# Power.net
KiCad netlist of a schematic drawn in Altium Designer
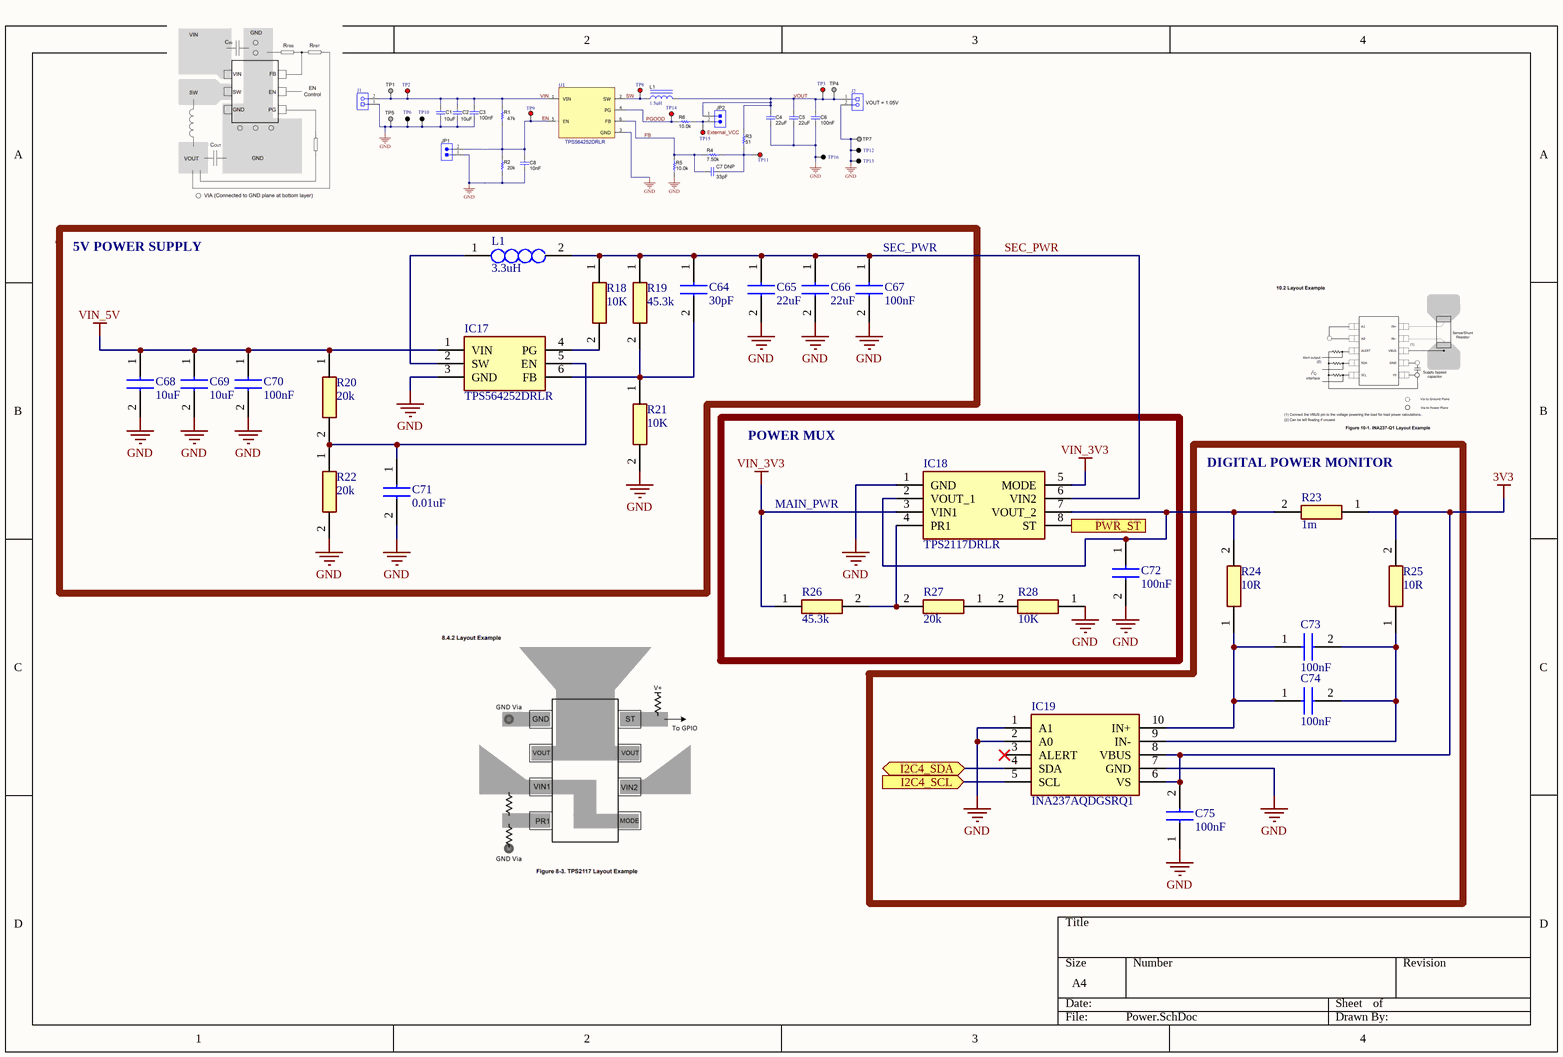
[diagram p0: Power.SchDoc]

(export (version "E")
  (design (tool "Eeschema 10.0.6"))
  (components
    (comp (ref "C64")
      (value "30pF")
      (footprint "RT_IS:C0603")
      (description "30 pF ±1% 50V Ceramic Capacitor X8R 0603 (1608 Metric)")
      (fields
        (field (name "MANUFACTURER_PART_NUMBER") "C0603C300F5HACAUTO")
        (field (name "MOUSER PART NUMBER") "80-C0603C300F5HAUTO")
      )
      (libsource (lib "*") (part "C0603C300F5HACAUTO"))
    )
    (comp (ref "C65")
      (value "22uF")
      (footprint "RT_IS:CAPC1608X90N")
      (description "22 µF ±20% 10V Ceramic Capacitor X5R 0603 (1608 Metric)")
      (fields
        (field (name "MANUFACTURER_PART_NUMBER") "GRT188R61A226ME13D")
        (field (name "MOUSER PART NUMBER") "81-GRT188R61A226ME13")
      )
      (libsource (lib "*") (part "GRT188R61A226ME13D"))
    )
    (comp (ref "C66")
      (value "22uF")
      (footprint "RT_IS:CAPC1608X90N")
      (description "22 µF ±20% 10V Ceramic Capacitor X5R 0603 (1608 Metric)")
      (fields
        (field (name "MANUFACTURER_PART_NUMBER") "GRT188R61A226ME13D")
        (field (name "MOUSER PART NUMBER") "81-GRT188R61A226ME13")
      )
      (libsource (lib "*") (part "GRT188R61A226ME13D"))
    )
    (comp (ref "C67")
      (value "100nF")
      (footprint "RT_IS:CAPC1608X95N")
      (description "0.1 µF ±20% 16V Ceramic Capacitor X7R 0603 (1608 Metric)")
      (fields (field (name "MANUFACTURER_PART_NUMBER") "C0603C104M4RAC7867"))
      (libsource (lib "*") (part "C0603C104M4RAC7867"))
    )
    (comp (ref "C68")
      (value "10uF")
      (footprint "RT_IS:CAPC1608X90N")
      (description "CAP CER 10UF 10V X7T 0603")
      (fields
        (field (name "MANUFACTURER_PART_NUMBER") "GRM188D71A106KA73D")
        (field (name "MOUSER PART NUMBER") "81-GRM188D71A106KA3D")
      )
      (libsource (lib "*") (part "GRM188D71A106KA73D"))
    )
    (comp (ref "C69")
      (value "10uF")
      (footprint "RT_IS:CAPC1608X90N")
      (description "CAP CER 10UF 10V X7T 0603")
      (fields
        (field (name "MANUFACTURER_PART_NUMBER") "GRM188D71A106KA73D")
        (field (name "MOUSER PART NUMBER") "81-GRM188D71A106KA3D")
      )
      (libsource (lib "*") (part "GRM188D71A106KA73D"))
    )
    (comp (ref "C70")
      (value "100nF")
      (footprint "RT_IS:CAPC1608X95N")
      (description "0.1 µF ±20% 16V Ceramic Capacitor X7R 0603 (1608 Metric)")
      (fields (field (name "MANUFACTURER_PART_NUMBER") "C0603C104M4RAC7867"))
      (libsource (lib "*") (part "C0603C104M4RAC7867"))
    )
    (comp (ref "C71")
      (value "0.01uF")
      (footprint "RT_IS:C0603")
      (description "10000 pF ±10% 63V Ceramic Capacitor X7R 0603 (1608 Metric)")
      (fields
        (field (name "MANUFACTURER_PART_NUMBER") "C0603C103KMRECAUTO")
        (field (name "MOUSER PART NUMBER") "80-C0603C103KMREAUTO")
      )
      (libsource (lib "*") (part "C0603C103KMRECAUTO"))
    )
    (comp (ref "C72")
      (value "100nF")
      (footprint "RT_IS:CAPC1608X95N")
      (description "0.1 µF ±20% 16V Ceramic Capacitor X7R 0603 (1608 Metric)")
      (fields (field (name "MANUFACTURER_PART_NUMBER") "C0603C104M4RAC7867"))
      (libsource (lib "*") (part "C0603C104M4RAC7867"))
    )
    (comp (ref "C73")
      (value "100nF")
      (footprint "RT_IS:CAPC1608X95N")
      (description "0.1 µF ±20% 16V Ceramic Capacitor X7R 0603 (1608 Metric)")
      (fields (field (name "MANUFACTURER_PART_NUMBER") "C0603C104M4RAC7867"))
      (libsource (lib "*") (part "C0603C104M4RAC7867"))
    )
    (comp (ref "C74")
      (value "100nF")
      (footprint "RT_IS:CAPC1608X95N")
      (description "0.1 µF ±20% 16V Ceramic Capacitor X7R 0603 (1608 Metric)")
      (fields (field (name "MANUFACTURER_PART_NUMBER") "C0603C104M4RAC7867"))
      (libsource (lib "*") (part "C0603C104M4RAC7867"))
    )
    (comp (ref "C75")
      (value "100nF")
      (footprint "RT_IS:CAPC1608X95N")
      (description "0.1 µF ±20% 16V Ceramic Capacitor X7R 0603 (1608 Metric)")
      (fields (field (name "MANUFACTURER_PART_NUMBER") "C0603C104M4RAC7867"))
      (libsource (lib "*") (part "C0603C104M4RAC7867"))
    )
    (comp (ref "IC17")
      (value "TPS564252DRLR")
      (footprint "RT_IS:SOTFL50P160X60-6N")
      (description "TPS564252DRLR\r\nBuck Switching Regulator IC Positive Adjustable 0.6V 1 Output 4A SOT-563, SOT-666")
      (fields
        (field (name "MANUFACTURER_PART_NUMBER") "TPS564257DRLR")
        (field (name "MOUSER PART NUMBER") "595-TPS564257DRLR")
      )
      (libsource (lib "*") (part "TPS564257DRLR"))
    )
    (comp (ref "IC18")
      (value "TPS2117DRLR")
      (footprint "RT_IS:SOTFL50P160X60-8N")
      (description "Power Switch/Driver 1:1 N-Channel 4A SOT-583")
      (fields
        (field (name "MANUFACTURER_PART_NUMBER") "TPS2116DRLR")
        (field (name "MOUSER PART NUMBER") "595-TPS2116DRLR")
      )
      (libsource (lib "*") (part "TPS2116DRLR"))
    )
    (comp (ref "IC19")
      (value "INA237AQDGSRQ1")
      (footprint "RT_IS:SOP50P490X110-10N")
      (description "Power Supply Controller 10-VSSOP")
      (fields (field (name "MOUSER PART NUMBER") "595-INA237AQDGSRQ1"))
      (libsource (lib "*") (part "INA237AQDGSRQ1"))
    )
    (comp (ref "L1")
      (value "3.3uH")
      (footprint "RT_IS:INDPM5653X430N")
      (description "3.3 µH Shielded Wirewound Inductor 5.75 A 18.5mOhm 2-SMD")
      (fields
        (field (name "MANUFACTURER_PART_NUMBER") "744316330")
        (field (name "MOUSER PART NUMBER") "710-744316330")
      )
      (libsource (lib "*") (part "744316330"))
    )
    (comp (ref "R18")
      (value "10K")
      (footprint "RT_IS:RESC1508X50N")
      (description "10 kOhms ±1% 0.125W, 1/8W Chip Resistor 0603 (1608 Metric) Anti-Sulfur Thin Film")
      (fields
        (field (name "MANUFACTURER_PART_NUMBER") "RNCP0603FTD10K0")
        (field (name "MOUSER PART NUMBER") "708-RNCP0603FTD10K0")
      )
      (libsource (lib "*") (part "RNCP0603FTD10K0"))
    )
    (comp (ref "R19")
      (value "45.3k")
      (footprint "RT_IS:RESC1608X55N")
      (description "45.3 kOhms ±1% 0.1W, 1/10W Chip Resistor 0603 (1608 Metric) Automotive AEC-Q200 Thick Film")
      (fields (field (name "MANUFACTURER_PART_NUMBER") "RMCF0603FT45K3"))
      (libsource (lib "*") (part "RMCF0603FT45K3"))
    )
    (comp (ref "R20")
      (value "20k")
      (footprint "RT_IS:RESC1608X55N")
      (description "20 kOhms ±1% 0.1W, 1/10W Chip Resistor 0603 (1608 Metric) Automotive AEC-Q200 Thick Film")
      (fields
        (field (name "MANUFACTURER_PART_NUMBER") "ERJ-3EKF2002V")
        (field (name "MOUSER PART NUMBER") "667-ERJ-3EKF2002V")
      )
      (libsource (lib "*") (part "ERJ-3EKF2002V"))
    )
    (comp (ref "R21")
      (value "10K")
      (footprint "RT_IS:RESC1508X50N")
      (description "10 kOhms ±1% 0.125W, 1/8W Chip Resistor 0603 (1608 Metric) Anti-Sulfur Thin Film")
      (fields
        (field (name "MANUFACTURER_PART_NUMBER") "RNCP0603FTD10K0")
        (field (name "MOUSER PART NUMBER") "708-RNCP0603FTD10K0")
      )
      (libsource (lib "*") (part "RNCP0603FTD10K0"))
    )
    (comp (ref "R22")
      (value "20k")
      (footprint "RT_IS:RESC1608X55N")
      (description "20 kOhms ±1% 0.1W, 1/10W Chip Resistor 0603 (1608 Metric) Automotive AEC-Q200 Thick Film")
      (fields
        (field (name "MANUFACTURER_PART_NUMBER") "ERJ-3EKF2002V")
        (field (name "MOUSER PART NUMBER") "667-ERJ-3EKF2002V")
      )
      (libsource (lib "*") (part "ERJ-3EKF2002V"))
    )
    (comp (ref "R23")
      (value "1m")
      (footprint "RT_IS:RESC2012X80N")
      (fields
        (field (name "MANUFACTURER_PART_NUMBER") "CRF0805-FZ-R001ELF")
        (field (name "MOUSER PART NUMBER") "652-CRF0805FZR001ELF")
      )
      (libsource (lib "*") (part "CRF0805-FZ-R001ELF"))
    )
    (comp (ref "R24")
      (value "10R")
      (footprint "RT_IS:RESC1608X55N")
      (description "10 Ohms ±1% 0.1W, 1/10W Chip Resistor 0603 (1608 Metric) Automotive AEC-Q200 Thick Film")
      (fields
        (field (name "MANUFACTURER_PART_NUMBER") "ERJ-3EKF10R0V")
        (field (name "MOUSER PART NUMBER") "667-ERJ-3EKF10R0V")
      )
      (libsource (lib "*") (part "ERJ-3EKF10R0V"))
    )
    (comp (ref "R25")
      (value "10R")
      (footprint "RT_IS:RESC1608X55N")
      (description "10 Ohms ±1% 0.1W, 1/10W Chip Resistor 0603 (1608 Metric) Automotive AEC-Q200 Thick Film")
      (fields
        (field (name "MANUFACTURER_PART_NUMBER") "ERJ-3EKF10R0V")
        (field (name "MOUSER PART NUMBER") "667-ERJ-3EKF10R0V")
      )
      (libsource (lib "*") (part "ERJ-3EKF10R0V"))
    )
    (comp (ref "R26")
      (value "45.3k")
      (footprint "RT_IS:RESC1608X55N")
      (description "45.3 kOhms ±1% 0.1W, 1/10W Chip Resistor 0603 (1608 Metric) Automotive AEC-Q200 Thick Film")
      (fields (field (name "MANUFACTURER_PART_NUMBER") "RMCF0603FT45K3"))
      (libsource (lib "") (part "RMCF0603FT45K3_1"))
    )
    (comp (ref "R27")
      (value "20k")
      (footprint "RT_IS:RESC1608X55N")
      (description "20 kOhms ±1% 0.1W, 1/10W Chip Resistor 0603 (1608 Metric) Automotive AEC-Q200 Thick Film")
      (fields
        (field (name "MANUFACTURER_PART_NUMBER") "ERJ-3EKF2002V")
        (field (name "MOUSER PART NUMBER") "667-ERJ-3EKF2002V")
      )
      (libsource (lib "") (part "ERJ-3EKF2002V_1"))
    )
    (comp (ref "R28")
      (value "10K")
      (footprint "RT_IS:RESC1508X50N")
      (description "10 kOhms ±1% 0.125W, 1/8W Chip Resistor 0603 (1608 Metric) Anti-Sulfur Thin Film")
      (fields
        (field (name "MANUFACTURER_PART_NUMBER") "RNCP0603FTD10K0")
        (field (name "MOUSER PART NUMBER") "708-RNCP0603FTD10K0")
      )
      (libsource (lib "") (part "RNCP0603FTD10K0_1"))
    )
  )
  (nets
    (net (code "1") (name "/I2C4_SCL") (class "Default")
      (node (ref "IC19") (pin "5") (pinfunction "SCL_5") (pintype "passive"))
    )
    (net (code "2") (name "/I2C4_SDA") (class "Default")
      (node (ref "IC19") (pin "4") (pinfunction "SDA_4") (pintype "passive"))
    )
    (net (code "3") (name "/PWR_ST") (class "Default")
      (node (ref "IC18") (pin "8") (pinfunction "ST_8") (pintype "passive"))
    )
    (net (code "4") (name "/SEC_PWR") (class "Default")
      (node (ref "C64") (pin "1") (pinfunction "1_1") (pintype "passive"))
      (node (ref "C65") (pin "1") (pinfunction "1_1") (pintype "passive"))
      (node (ref "C66") (pin "1") (pinfunction "1_1") (pintype "passive"))
      (node (ref "C67") (pin "1") (pinfunction "1_1") (pintype "passive"))
      (node (ref "IC18") (pin "6") (pinfunction "VIN2_6") (pintype "passive"))
      (node (ref "L1") (pin "2") (pinfunction "2_2") (pintype "passive"))
      (node (ref "R18") (pin "1") (pinfunction "1_1") (pintype "passive"))
      (node (ref "R19") (pin "1") (pinfunction "1_1") (pintype "passive"))
    )
    (net (code "5") (name "3V3") (class "Default")
      (node (ref "C75") (pin "2") (pinfunction "2_2") (pintype "passive"))
      (node (ref "IC19") (pin "6") (pinfunction "VS_6") (pintype "passive"))
      (node (ref "IC19") (pin "8") (pinfunction "VBUS_8") (pintype "passive"))
      (node (ref "R23") (pin "1") (pinfunction "1_1") (pintype "passive"))
      (node (ref "R25") (pin "2") (pinfunction "2_2") (pintype "passive"))
    )
    (net (code "6") (name "GND") (class "Default")
      (node (ref "C65") (pin "2") (pinfunction "2_2") (pintype "passive"))
      (node (ref "C66") (pin "2") (pinfunction "2_2") (pintype "passive"))
      (node (ref "C67") (pin "2") (pinfunction "2_2") (pintype "passive"))
      (node (ref "C68") (pin "2") (pinfunction "2_2") (pintype "passive"))
      (node (ref "C69") (pin "2") (pinfunction "2_2") (pintype "passive"))
      (node (ref "C70") (pin "2") (pinfunction "2_2") (pintype "passive"))
      (node (ref "C71") (pin "2") (pinfunction "2_2") (pintype "passive"))
      (node (ref "C72") (pin "2") (pinfunction "2_2") (pintype "passive"))
      (node (ref "C75") (pin "1") (pinfunction "1_1") (pintype "passive"))
      (node (ref "IC17") (pin "3") (pinfunction "GND_3") (pintype "passive"))
      (node (ref "IC18") (pin "1") (pinfunction "GND_1") (pintype "passive"))
      (node (ref "IC19") (pin "1") (pinfunction "A1_1") (pintype "passive"))
      (node (ref "IC19") (pin "2") (pinfunction "A0_2") (pintype "passive"))
      (node (ref "IC19") (pin "7") (pinfunction "GND_7") (pintype "passive"))
      (node (ref "R21") (pin "2") (pinfunction "2_2") (pintype "passive"))
      (node (ref "R22") (pin "2") (pinfunction "2_2") (pintype "passive"))
      (node (ref "R28") (pin "1") (pinfunction "1_1") (pintype "passive"))
    )
    (net (code "7") (name "Net-(IC17-EN)") (class "Default")
      (node (ref "C71") (pin "1") (pinfunction "1_1") (pintype "passive"))
      (node (ref "IC17") (pin "5") (pinfunction "EN_5") (pintype "passive"))
      (node (ref "R20") (pin "2") (pinfunction "2_2") (pintype "passive"))
      (node (ref "R22") (pin "1") (pinfunction "1_1") (pintype "passive"))
    )
    (net (code "8") (name "Net-(IC17-FB)") (class "Default")
      (node (ref "C64") (pin "2") (pinfunction "2_2") (pintype "passive"))
      (node (ref "IC17") (pin "6") (pinfunction "FB_6") (pintype "passive"))
      (node (ref "R19") (pin "2") (pinfunction "2_2") (pintype "passive"))
      (node (ref "R21") (pin "1") (pinfunction "1_1") (pintype "passive"))
    )
    (net (code "9") (name "Net-(IC17-PG)") (class "Default")
      (node (ref "IC17") (pin "4") (pinfunction "PG_4") (pintype "passive"))
      (node (ref "R18") (pin "2") (pinfunction "2_2") (pintype "passive"))
    )
    (net (code "10") (name "Net-(IC17-SW)") (class "Default")
      (node (ref "IC17") (pin "2") (pinfunction "SW_2") (pintype "passive"))
      (node (ref "L1") (pin "1") (pinfunction "1_1") (pintype "passive"))
    )
    (net (code "11") (name "Net-(IC18-PR1)") (class "Default")
      (node (ref "IC18") (pin "4") (pinfunction "PR1_4") (pintype "passive"))
      (node (ref "R26") (pin "2") (pinfunction "2_2") (pintype "passive"))
      (node (ref "R27") (pin "2") (pinfunction "2_2") (pintype "passive"))
    )
    (net (code "12") (name "Net-(IC18-VOUT_1)") (class "Default")
      (node (ref "C72") (pin "1") (pinfunction "1_1") (pintype "passive"))
      (node (ref "IC18") (pin "2") (pinfunction "VOUT_1_2") (pintype "passive"))
      (node (ref "IC18") (pin "7") (pinfunction "VOUT_2_7") (pintype "passive"))
      (node (ref "R23") (pin "2") (pinfunction "2_2") (pintype "passive"))
      (node (ref "R24") (pin "2") (pinfunction "2_2") (pintype "passive"))
    )
    (net (code "13") (name "Net-(IC19-IN+)") (class "Default")
      (node (ref "C73") (pin "1") (pinfunction "1_1") (pintype "passive"))
      (node (ref "C74") (pin "1") (pinfunction "1_1") (pintype "passive"))
      (node (ref "IC19") (pin "10") (pinfunction "IN+_10") (pintype "passive"))
      (node (ref "R24") (pin "1") (pinfunction "1_1") (pintype "passive"))
    )
    (net (code "14") (name "Net-(IC19-IN-)") (class "Default")
      (node (ref "C73") (pin "2") (pinfunction "2_2") (pintype "passive"))
      (node (ref "C74") (pin "2") (pinfunction "2_2") (pintype "passive"))
      (node (ref "IC19") (pin "9") (pinfunction "IN-_9") (pintype "passive"))
      (node (ref "R25") (pin "1") (pinfunction "1_1") (pintype "passive"))
    )
    (net (code "15") (name "Net-(R27-Pad1)") (class "Default")
      (node (ref "R27") (pin "1") (pinfunction "1_1") (pintype "passive"))
      (node (ref "R28") (pin "2") (pinfunction "2_2") (pintype "passive"))
    )
    (net (code "16") (name "VIN_3V3") (class "Default")
      (node (ref "IC18") (pin "3") (pinfunction "VIN1_3") (pintype "passive"))
      (node (ref "IC18") (pin "5") (pinfunction "MODE_5") (pintype "passive"))
      (node (ref "R26") (pin "1") (pinfunction "1_1") (pintype "passive"))
    )
    (net (code "17") (name "VIN_5V") (class "Default")
      (node (ref "C68") (pin "1") (pinfunction "1_1") (pintype "passive"))
      (node (ref "C69") (pin "1") (pinfunction "1_1") (pintype "passive"))
      (node (ref "C70") (pin "1") (pinfunction "1_1") (pintype "passive"))
      (node (ref "IC17") (pin "1") (pinfunction "VIN_1") (pintype "passive"))
      (node (ref "R20") (pin "1") (pinfunction "1_1") (pintype "passive"))
    )
    (net (code "18") (name "unconnected-(IC19-ALERT-Pad3)") (class "Default")
      (node (ref "IC19") (pin "3") (pinfunction "ALERT_3") (pintype "passive+no_connect"))
    )
  )
)
